# MCU.net
KiCad netlist of a schematic drawn in Altium Designer
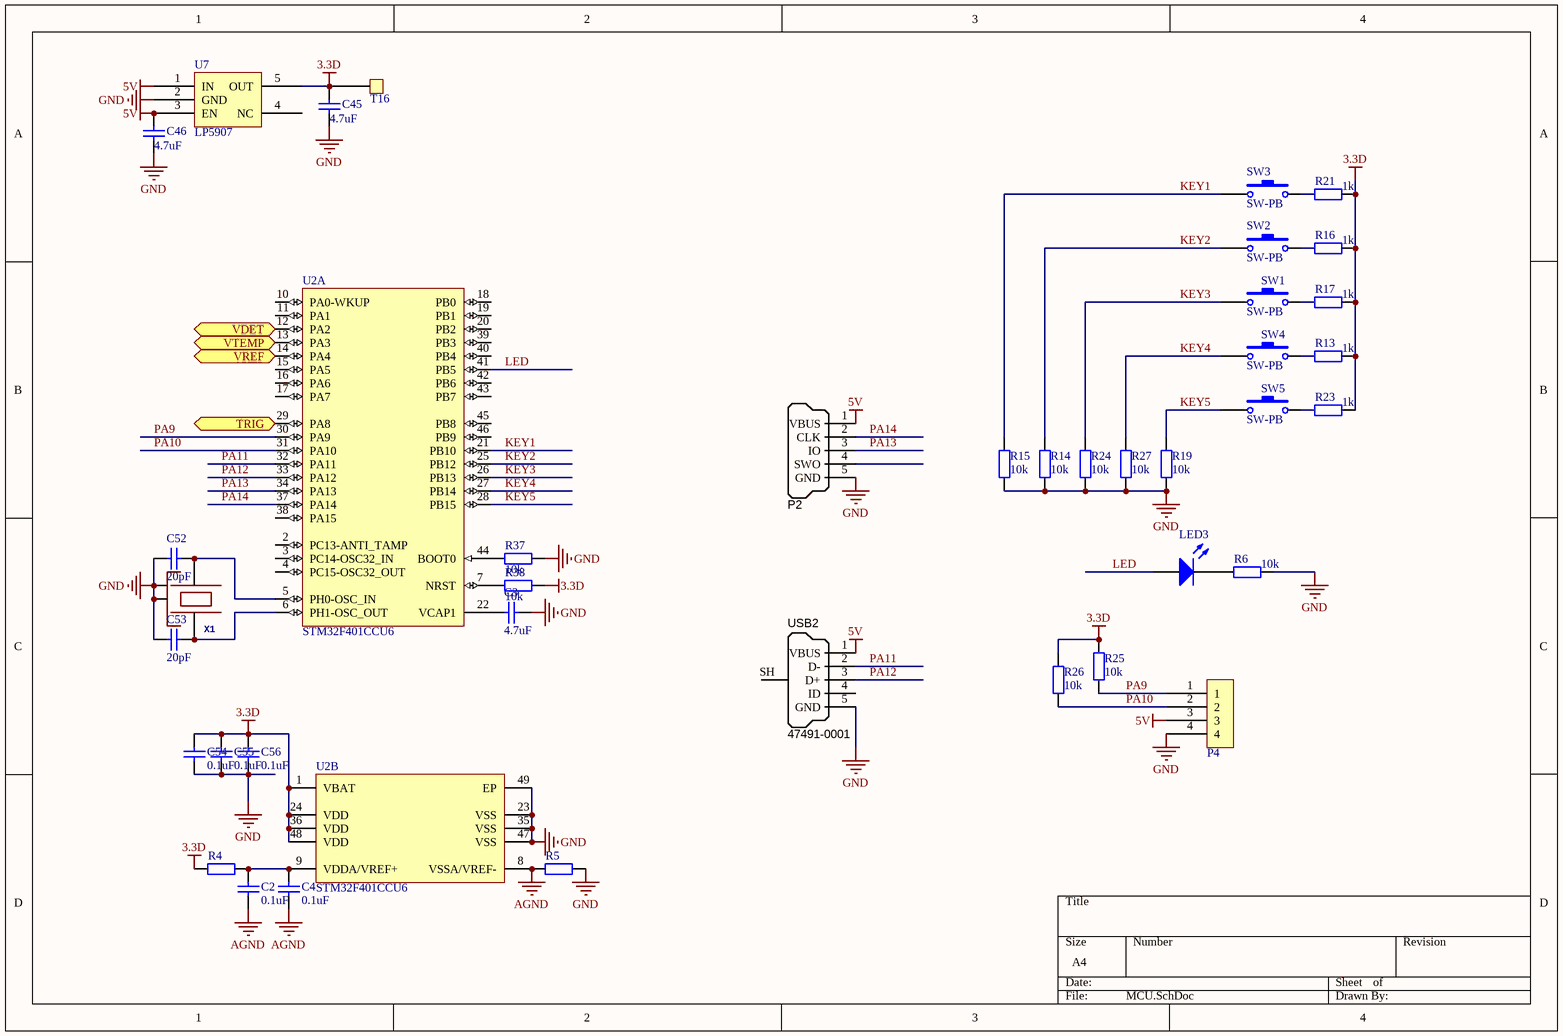
[diagram p0: MCU.SchDoc]

(export (version "E")
  (design (tool "Eeschema 10.0.6"))
  (components
    (comp (ref "C2")
      (value "0.1uF")
      (footprint "0402")
      (description "Capacitor")
      (fields (field (name "Comment") "Cap") (field (name "PUBLISHER") "Altium Limited"))
      (libsource (lib "RTC6705") (part "Cap"))
    )
    (comp (ref "C3")
      (value "4.7uF")
      (footprint "0603")
      (description "Capacitor")
      (fields (field (name "Comment") "Cap") (field (name "PUBLISHER") "Altium Limited"))
      (libsource (lib "RTC6705") (part "Cap"))
    )
    (comp (ref "C4")
      (value "0.1uF")
      (footprint "0402")
      (description "Capacitor")
      (fields (field (name "Comment") "Cap") (field (name "PUBLISHER") "Altium Limited"))
      (libsource (lib "RTC6705") (part "Cap"))
    )
    (comp (ref "C45")
      (value "4.7uF")
      (footprint "0603")
      (description "Capacitor")
      (fields (field (name "PUBLISHER") "Altium Limited"))
      (libsource (lib "RTC6705") (part "Cap"))
    )
    (comp (ref "C46")
      (value "4.7uF")
      (footprint "0603")
      (description "Capacitor")
      (fields (field (name "PUBLISHER") "Altium Limited"))
      (libsource (lib "RTC6705") (part "Cap"))
    )
    (comp (ref "C52")
      (value "20pF")
      (footprint "0402")
      (description "Capacitor")
      (fields (field (name "Comment") "Cap") (field (name "PUBLISHER") "Altium Limited"))
      (libsource (lib "RTC6705") (part "Cap"))
    )
    (comp (ref "C53")
      (value "20pF")
      (footprint "0402")
      (description "Capacitor")
      (fields (field (name "Comment") "Cap") (field (name "PUBLISHER") "Altium Limited"))
      (libsource (lib "RTC6705") (part "Cap"))
    )
    (comp (ref "C54")
      (value "0.1uF")
      (footprint "0402")
      (description "Capacitor")
      (fields (field (name "Comment") "Cap") (field (name "PUBLISHER") "Altium Limited"))
      (libsource (lib "RTC6705") (part "Cap"))
    )
    (comp (ref "C55")
      (value "0.1uF")
      (footprint "0402")
      (description "Capacitor")
      (fields (field (name "Comment") "Cap") (field (name "PUBLISHER") "Altium Limited"))
      (libsource (lib "RTC6705") (part "Cap"))
    )
    (comp (ref "C56")
      (value "0.1uF")
      (footprint "0402")
      (description "Capacitor")
      (fields (field (name "Comment") "Cap") (field (name "PUBLISHER") "Altium Limited"))
      (libsource (lib "RTC6705") (part "Cap"))
    )
    (comp (ref "LED3")
      (value "LED0")
      (footprint "0603")
      (description "Typical INFRARED GaAs LED")
      (fields (field (name "PUBLISHER") "Altium Limited"))
      (libsource (lib "Miscellaneous Devices") (part "LED0"))
    )
    (comp (ref "P2")
      (value "SWD_MicroUSB")
      (footprint "MICRO-YZX")
      (description "Connector SMD USB Micro Type B middle mount")
      (libsource (lib "sch") (part "SWD_MicroUSB"))
    )
    (comp (ref "P4") (value "UART/I2C") (footprint "4pSocket") (libsource (lib "sch") (part "4PSocket")))
    (comp (ref "R4")
      (value "0R/FB")
      (footprint "0402")
      (description "Resistor")
      (fields (field (name "PUBLISHER") "Altium Limited"))
      (libsource (lib "RTC6705") (part "Res2"))
    )
    (comp (ref "R5")
      (value "0R/FB")
      (footprint "0402")
      (description "Resistor")
      (fields (field (name "PUBLISHER") "Altium Limited"))
      (libsource (lib "RTC6705") (part "Res2"))
    )
    (comp (ref "R6")
      (value "10k")
      (footprint "0402")
      (description "Resistor")
      (fields (field (name "PUBLISHER") "Altium Limited"))
      (libsource (lib "Miscellaneous Devices") (part "Res2"))
    )
    (comp (ref "R13")
      (value "1k")
      (footprint "0402")
      (description "Resistor")
      (fields (field (name "PUBLISHER") "Altium Limited"))
      (libsource (lib "Miscellaneous Devices") (part "Res2"))
    )
    (comp (ref "R14")
      (value "10k")
      (footprint "0402")
      (description "Resistor")
      (fields (field (name "PUBLISHER") "Altium Limited"))
      (libsource (lib "") (part "Res2_1"))
    )
    (comp (ref "R15")
      (value "10k")
      (footprint "0402")
      (description "Resistor")
      (fields (field (name "PUBLISHER") "Altium Limited"))
      (libsource (lib "") (part "Res2_1"))
    )
    (comp (ref "R16")
      (value "1k")
      (footprint "0402")
      (description "Resistor")
      (fields (field (name "PUBLISHER") "Altium Limited"))
      (libsource (lib "Miscellaneous Devices") (part "Res2"))
    )
    (comp (ref "R17")
      (value "1k")
      (footprint "0402")
      (description "Resistor")
      (fields (field (name "PUBLISHER") "Altium Limited"))
      (libsource (lib "Miscellaneous Devices") (part "Res2"))
    )
    (comp (ref "R19")
      (value "10k")
      (footprint "0402")
      (description "Resistor")
      (fields (field (name "PUBLISHER") "Altium Limited"))
      (libsource (lib "") (part "Res2_1"))
    )
    (comp (ref "R21")
      (value "1k")
      (footprint "0402")
      (description "Resistor")
      (fields (field (name "PUBLISHER") "Altium Limited"))
      (libsource (lib "Miscellaneous Devices") (part "Res2"))
    )
    (comp (ref "R23")
      (value "1k")
      (footprint "0402")
      (description "Resistor")
      (fields (field (name "PUBLISHER") "Altium Limited"))
      (libsource (lib "Miscellaneous Devices") (part "Res2"))
    )
    (comp (ref "R24")
      (value "10k")
      (footprint "0402")
      (description "Resistor")
      (fields (field (name "PUBLISHER") "Altium Limited"))
      (libsource (lib "") (part "Res2_1"))
    )
    (comp (ref "R25")
      (value "10k")
      (footprint "0402")
      (description "Resistor")
      (fields (field (name "PUBLISHER") "Altium Limited"))
      (libsource (lib "") (part "Res2_1"))
    )
    (comp (ref "R26")
      (value "10k")
      (footprint "0402")
      (description "Resistor")
      (fields (field (name "PUBLISHER") "Altium Limited"))
      (libsource (lib "") (part "Res2_1"))
    )
    (comp (ref "R27")
      (value "10k")
      (footprint "0402")
      (description "Resistor")
      (fields (field (name "PUBLISHER") "Altium Limited"))
      (libsource (lib "") (part "Res2_1"))
    )
    (comp (ref "R37")
      (value "10k")
      (footprint "0402")
      (description "Resistor")
      (fields (field (name "Comment") "Res2") (field (name "PUBLISHER") "Altium Limited"))
      (libsource (lib "") (part "Res2_1"))
    )
    (comp (ref "R38")
      (value "10k")
      (footprint "0402")
      (description "Resistor")
      (fields (field (name "Comment") "Res2") (field (name "PUBLISHER") "Altium Limited"))
      (libsource (lib "RTC6705") (part "Res2"))
    )
    (comp (ref "SW1")
      (value "SW-PB")
      (footprint "SW3x4")
      (description "Switch")
      (fields (field (name "PUBLISHER") "Altium Limited"))
      (libsource (lib "Miscellaneous Devices") (part "SW-PB"))
    )
    (comp (ref "SW2")
      (value "SW-PB")
      (footprint "SW3x4")
      (description "Switch")
      (fields (field (name "PUBLISHER") "Altium Limited"))
      (libsource (lib "Miscellaneous Devices") (part "SW-PB"))
    )
    (comp (ref "SW3")
      (value "SW-PB")
      (footprint "SW3x4")
      (description "Switch")
      (fields (field (name "PUBLISHER") "Altium Limited"))
      (libsource (lib "Miscellaneous Devices") (part "SW-PB"))
    )
    (comp (ref "SW4")
      (value "SW-PB")
      (footprint "SW3x4")
      (description "Switch")
      (fields (field (name "PUBLISHER") "Altium Limited"))
      (libsource (lib "Miscellaneous Devices") (part "SW-PB"))
    )
    (comp (ref "SW5")
      (value "SW-PB")
      (footprint "SW3x4")
      (description "Switch")
      (fields (field (name "PUBLISHER") "Altium Limited"))
      (libsource (lib "Miscellaneous Devices") (part "SW-PB"))
    )
    (comp (ref "T16") (value "TestPad") (footprint "TestPad - 1mm") (libsource (lib "sch") (part "TestPad")))
    (comp (ref "U2")
      (value "STM32F401CCU6")
      (footprint "STM-UFQFPN48_N")
      (fields (field (name "MANUFACTURER") "STMicroelectronics"))
      (libsource (lib "STMicroelectronics STM32 F4") (part "STM32F401CCU6"))
    )
    (comp (ref "U7") (value "LP5907") (footprint "SOT23-5") (libsource (lib "RTC6705") (part "LP5907")))
    (comp (ref "USB2")
      (value "USB Micro Type B")
      (footprint "MICRO-YZX")
      (description "Connector SMD USB Micro Type B middle mount")
      (fields (field (name "MANUFACTURER PART NUMBER 1") "47491-0001"))
      (libsource (lib "PBL - Connectors") (part "USB_Micro_TypeB"))
    )
    (comp (ref "X1")
      (value "24.000 KHz 3.2x2.5mm 8-10pf")
      (footprint "OSCILLATOR-3.2X2.5")
      (description "Crystal Oscillator in 3.2x2.5 SMD")
      (libsource (lib "pixhawk2") (part "OSCILLATOR-3.2X2.5"))
    )
  )
  (nets
    (net (code "1") (name "/KEY1") (class "Default")
      (node (ref "R15") (pin "2") (pinfunction "2_2") (pintype "passive"))
      (node (ref "SW3") (pin "1") (pinfunction "1_1") (pintype "passive"))
      (node (ref "U2") (pin "21") (pinfunction "PB10_21") (pintype "bidirectional"))
    )
    (net (code "2") (name "/KEY2") (class "Default")
      (node (ref "R14") (pin "2") (pinfunction "2_2") (pintype "passive"))
      (node (ref "SW2") (pin "1") (pinfunction "1_1") (pintype "passive"))
      (node (ref "U2") (pin "25") (pinfunction "PB12_25") (pintype "bidirectional"))
    )
    (net (code "3") (name "/KEY3") (class "Default")
      (node (ref "R24") (pin "2") (pinfunction "2_2") (pintype "passive"))
      (node (ref "SW1") (pin "1") (pinfunction "1_1") (pintype "passive"))
      (node (ref "U2") (pin "26") (pinfunction "PB13_26") (pintype "bidirectional"))
    )
    (net (code "4") (name "/KEY4") (class "Default")
      (node (ref "R27") (pin "2") (pinfunction "2_2") (pintype "passive"))
      (node (ref "SW4") (pin "1") (pinfunction "1_1") (pintype "passive"))
      (node (ref "U2") (pin "27") (pinfunction "PB14_27") (pintype "bidirectional"))
    )
    (net (code "5") (name "/KEY5") (class "Default")
      (node (ref "R19") (pin "2") (pinfunction "2_2") (pintype "passive"))
      (node (ref "SW5") (pin "1") (pinfunction "1_1") (pintype "passive"))
      (node (ref "U2") (pin "28") (pinfunction "PB15_28") (pintype "bidirectional"))
    )
    (net (code "6") (name "/LED") (class "Default")
      (node (ref "LED3") (pin "1") (pinfunction "A_1") (pintype "passive"))
      (node (ref "U2") (pin "41") (pinfunction "PB5_41") (pintype "bidirectional"))
    )
    (net (code "7") (name "/PA9") (class "Default")
      (node (ref "P4") (pin "1") (pinfunction "1_1") (pintype "passive"))
      (node (ref "R25") (pin "1") (pinfunction "1_1") (pintype "passive"))
      (node (ref "U2") (pin "30") (pinfunction "PA9_30") (pintype "bidirectional"))
    )
    (net (code "8") (name "/PA10") (class "Default")
      (node (ref "P4") (pin "2") (pinfunction "2_2") (pintype "passive"))
      (node (ref "R26") (pin "1") (pinfunction "1_1") (pintype "passive"))
      (node (ref "U2") (pin "31") (pinfunction "PA10_31") (pintype "bidirectional"))
    )
    (net (code "9") (name "/PA11") (class "Default")
      (node (ref "U2") (pin "32") (pinfunction "PA11_32") (pintype "bidirectional"))
      (node (ref "USB2") (pin "2") (pinfunction "D-_2") (pintype "passive"))
    )
    (net (code "10") (name "/PA12") (class "Default")
      (node (ref "U2") (pin "33") (pinfunction "PA12_33") (pintype "bidirectional"))
      (node (ref "USB2") (pin "3") (pinfunction "D+_3") (pintype "passive"))
    )
    (net (code "11") (name "/PA13") (class "Default")
      (node (ref "P2") (pin "3") (pinfunction "IO_3") (pintype "passive"))
      (node (ref "U2") (pin "34") (pinfunction "PA13_34") (pintype "bidirectional"))
    )
    (net (code "12") (name "/PA14") (class "Default")
      (node (ref "P2") (pin "2") (pinfunction "CLK_2") (pintype "passive"))
      (node (ref "U2") (pin "37") (pinfunction "PA14_37") (pintype "bidirectional"))
    )
    (net (code "13") (name "/TRIG") (class "Default")
      (node (ref "U2") (pin "29") (pinfunction "PA8_29") (pintype "bidirectional"))
    )
    (net (code "14") (name "/VDET") (class "Default")
      (node (ref "U2") (pin "12") (pinfunction "PA2_12") (pintype "bidirectional"))
    )
    (net (code "15") (name "/VREF") (class "Default")
      (node (ref "U2") (pin "14") (pinfunction "PA4_14") (pintype "bidirectional"))
    )
    (net (code "16") (name "/VTEMP") (class "Default")
      (node (ref "U2") (pin "13") (pinfunction "PA3_13") (pintype "bidirectional"))
    )
    (net (code "17") (name "3.3D") (class "Default")
      (node (ref "C45") (pin "2") (pinfunction "2_2") (pintype "passive"))
      (node (ref "C54") (pin "2") (pinfunction "2_2") (pintype "passive"))
      (node (ref "C55") (pin "2") (pinfunction "2_2") (pintype "passive"))
      (node (ref "C56") (pin "2") (pinfunction "2_2") (pintype "passive"))
      (node (ref "R13") (pin "2") (pinfunction "2_2") (pintype "passive"))
      (node (ref "R16") (pin "2") (pinfunction "2_2") (pintype "passive"))
      (node (ref "R17") (pin "2") (pinfunction "2_2") (pintype "passive"))
      (node (ref "R21") (pin "2") (pinfunction "2_2") (pintype "passive"))
      (node (ref "R23") (pin "2") (pinfunction "2_2") (pintype "passive"))
      (node (ref "R25") (pin "2") (pinfunction "2_2") (pintype "passive"))
      (node (ref "R26") (pin "2") (pinfunction "2_2") (pintype "passive"))
      (node (ref "R38") (pin "1") (pinfunction "1_1") (pintype "passive"))
      (node (ref "R4") (pin "2") (pinfunction "2_2") (pintype "passive"))
      (node (ref "T16") (pin "1") (pinfunction "3_1") (pintype "passive"))
      (node (ref "U2") (pin "1") (pinfunction "VBAT_1") (pintype "power_in"))
      (node (ref "U2") (pin "24") (pinfunction "VDD_24") (pintype "power_in"))
      (node (ref "U2") (pin "36") (pinfunction "VDD_36") (pintype "power_in"))
      (node (ref "U2") (pin "48") (pinfunction "VDD_48") (pintype "power_in"))
      (node (ref "U7") (pin "5") (pinfunction "OUT_5") (pintype "passive"))
    )
    (net (code "18") (name "5V") (class "Default")
      (node (ref "C46") (pin "2") (pinfunction "2_2") (pintype "passive"))
      (node (ref "P2") (pin "1") (pinfunction "VBUS_1") (pintype "passive"))
      (node (ref "P4") (pin "3") (pinfunction "3_3") (pintype "passive"))
      (node (ref "U7") (pin "1") (pinfunction "IN_1") (pintype "passive"))
      (node (ref "U7") (pin "3") (pinfunction "EN_3") (pintype "passive"))
      (node (ref "USB2") (pin "1") (pinfunction "VBUS_1") (pintype "passive"))
    )
    (net (code "19") (name "AGND") (class "Default")
      (node (ref "C2") (pin "1") (pinfunction "1_1") (pintype "passive"))
      (node (ref "C4") (pin "1") (pinfunction "1_1") (pintype "passive"))
      (node (ref "R5") (pin "2") (pinfunction "2_2") (pintype "passive"))
      (node (ref "U2") (pin "8") (pinfunction "VSSA/VREF-_8") (pintype "power_in"))
    )
    (net (code "20") (name "GND") (class "Default")
      (node (ref "C3") (pin "1") (pinfunction "1_1") (pintype "passive"))
      (node (ref "C45") (pin "1") (pinfunction "1_1") (pintype "passive"))
      (node (ref "C46") (pin "1") (pinfunction "1_1") (pintype "passive"))
      (node (ref "C52") (pin "1") (pinfunction "1_1") (pintype "passive"))
      (node (ref "C53") (pin "1") (pinfunction "1_1") (pintype "passive"))
      (node (ref "C54") (pin "1") (pinfunction "1_1") (pintype "passive"))
      (node (ref "C55") (pin "1") (pinfunction "1_1") (pintype "passive"))
      (node (ref "C56") (pin "1") (pinfunction "1_1") (pintype "passive"))
      (node (ref "P2") (pin "5") (pinfunction "GND_5") (pintype "passive"))
      (node (ref "P4") (pin "4") (pinfunction "4_4") (pintype "passive"))
      (node (ref "R14") (pin "1") (pinfunction "1_1") (pintype "passive"))
      (node (ref "R15") (pin "1") (pinfunction "1_1") (pintype "passive"))
      (node (ref "R19") (pin "1") (pinfunction "1_1") (pintype "passive"))
      (node (ref "R24") (pin "1") (pinfunction "1_1") (pintype "passive"))
      (node (ref "R27") (pin "1") (pinfunction "1_1") (pintype "passive"))
      (node (ref "R37") (pin "2") (pinfunction "2_2") (pintype "passive"))
      (node (ref "R5") (pin "1") (pinfunction "1_1") (pintype "passive"))
      (node (ref "R6") (pin "2") (pinfunction "2_2") (pintype "passive"))
      (node (ref "U2") (pin "23") (pinfunction "VSS_23") (pintype "power_in"))
      (node (ref "U2") (pin "35") (pinfunction "VSS_35") (pintype "power_in"))
      (node (ref "U2") (pin "47") (pinfunction "VSS_47") (pintype "power_in"))
      (node (ref "U2") (pin "49") (pinfunction "EP_49") (pintype "power_in"))
      (node (ref "U7") (pin "2") (pinfunction "GND_2") (pintype "passive"))
      (node (ref "USB2") (pin "5") (pinfunction "GND_5") (pintype "passive"))
      (node (ref "X1") (pin "2") (pinfunction "NC_2_2") (pintype "open_emitter"))
      (node (ref "X1") (pin "4") (pinfunction "NC_4_4") (pintype "open_emitter"))
    )
    (net (code "21") (name "Net-(LED3-K)") (class "Default")
      (node (ref "LED3") (pin "2") (pinfunction "K_2") (pintype "passive"))
      (node (ref "R6") (pin "1") (pinfunction "1_1") (pintype "passive"))
    )
    (net (code "22") (name "Net-(R13-Pad1)") (class "Default")
      (node (ref "R13") (pin "1") (pinfunction "1_1") (pintype "passive"))
      (node (ref "SW4") (pin "2") (pinfunction "2_2") (pintype "passive"))
    )
    (net (code "23") (name "Net-(R16-Pad1)") (class "Default")
      (node (ref "R16") (pin "1") (pinfunction "1_1") (pintype "passive"))
      (node (ref "SW2") (pin "2") (pinfunction "2_2") (pintype "passive"))
    )
    (net (code "24") (name "Net-(R17-Pad1)") (class "Default")
      (node (ref "R17") (pin "1") (pinfunction "1_1") (pintype "passive"))
      (node (ref "SW1") (pin "2") (pinfunction "2_2") (pintype "passive"))
    )
    (net (code "25") (name "Net-(R21-Pad1)") (class "Default")
      (node (ref "R21") (pin "1") (pinfunction "1_1") (pintype "passive"))
      (node (ref "SW3") (pin "2") (pinfunction "2_2") (pintype "passive"))
    )
    (net (code "26") (name "Net-(R23-Pad1)") (class "Default")
      (node (ref "R23") (pin "1") (pinfunction "1_1") (pintype "passive"))
      (node (ref "SW5") (pin "2") (pinfunction "2_2") (pintype "passive"))
    )
    (net (code "27") (name "Net-(U2A-BOOT0)") (class "Default")
      (node (ref "R37") (pin "1") (pinfunction "1_1") (pintype "passive"))
      (node (ref "U2") (pin "44") (pinfunction "BOOT0_44") (pintype "input"))
    )
    (net (code "28") (name "Net-(U2A-NRST)") (class "Default")
      (node (ref "R38") (pin "2") (pinfunction "2_2") (pintype "passive"))
      (node (ref "U2") (pin "7") (pinfunction "NRST_7") (pintype "bidirectional"))
    )
    (net (code "29") (name "Net-(U2A-PH0-OSC_IN)") (class "Default")
      (node (ref "C52") (pin "2") (pinfunction "2_2") (pintype "passive"))
      (node (ref "U2") (pin "5") (pinfunction "PH0-OSC_IN_5") (pintype "bidirectional"))
      (node (ref "X1") (pin "1") (pinfunction "1_1") (pintype "passive"))
    )
    (net (code "30") (name "Net-(U2A-PH1-OSC_OUT)") (class "Default")
      (node (ref "C53") (pin "2") (pinfunction "2_2") (pintype "passive"))
      (node (ref "U2") (pin "6") (pinfunction "PH1-OSC_OUT_6") (pintype "bidirectional"))
      (node (ref "X1") (pin "3") (pinfunction "3_3") (pintype "passive"))
    )
    (net (code "31") (name "Net-(U2A-VCAP1)") (class "Default")
      (node (ref "C3") (pin "2") (pinfunction "2_2") (pintype "passive"))
      (node (ref "U2") (pin "22") (pinfunction "VCAP1_22") (pintype "power_in"))
    )
    (net (code "32") (name "Net-(U2B-VDDA{slash}VREF+)") (class "Default")
      (node (ref "C2") (pin "2") (pinfunction "2_2") (pintype "passive"))
      (node (ref "C4") (pin "2") (pinfunction "2_2") (pintype "passive"))
      (node (ref "R4") (pin "1") (pinfunction "1_1") (pintype "passive"))
      (node (ref "U2") (pin "9") (pinfunction "VDDA/VREF+_9") (pintype "power_in"))
    )
    (net (code "33") (name "unconnected-(P2-SWO-Pad4)") (class "Default")
      (node (ref "P2") (pin "4") (pinfunction "SWO_4") (pintype "passive"))
    )
    (net (code "34") (name "unconnected-(U2A-PA0-WKUP-Pad10)") (class "Default")
      (node (ref "U2") (pin "10") (pinfunction "PA0-WKUP_10") (pintype "bidirectional"))
    )
    (net (code "35") (name "unconnected-(U2A-PA1-Pad11)") (class "Default")
      (node (ref "U2") (pin "11") (pinfunction "PA1_11") (pintype "bidirectional"))
    )
    (net (code "36") (name "unconnected-(U2A-PA5-Pad15)") (class "Default")
      (node (ref "U2") (pin "15") (pinfunction "PA5_15") (pintype "bidirectional"))
    )
    (net (code "37") (name "unconnected-(U2A-PA6-Pad16)") (class "Default")
      (node (ref "U2") (pin "16") (pinfunction "PA6_16") (pintype "bidirectional"))
    )
    (net (code "38") (name "unconnected-(U2A-PA7-Pad17)") (class "Default")
      (node (ref "U2") (pin "17") (pinfunction "PA7_17") (pintype "bidirectional"))
    )
    (net (code "39") (name "unconnected-(U2A-PA15-Pad38)") (class "Default")
      (node (ref "U2") (pin "38") (pinfunction "PA15_38") (pintype "bidirectional"))
    )
    (net (code "40") (name "unconnected-(U2A-PB0-Pad18)") (class "Default")
      (node (ref "U2") (pin "18") (pinfunction "PB0_18") (pintype "bidirectional"))
    )
    (net (code "41") (name "unconnected-(U2A-PB1-Pad19)") (class "Default")
      (node (ref "U2") (pin "19") (pinfunction "PB1_19") (pintype "bidirectional"))
    )
    (net (code "42") (name "unconnected-(U2A-PB2-Pad20)") (class "Default")
      (node (ref "U2") (pin "20") (pinfunction "PB2_20") (pintype "bidirectional"))
    )
    (net (code "43") (name "unconnected-(U2A-PB3-Pad39)") (class "Default")
      (node (ref "U2") (pin "39") (pinfunction "PB3_39") (pintype "bidirectional"))
    )
    (net (code "44") (name "unconnected-(U2A-PB4-Pad40)") (class "Default")
      (node (ref "U2") (pin "40") (pinfunction "PB4_40") (pintype "bidirectional"))
    )
    (net (code "45") (name "unconnected-(U2A-PB6-Pad42)") (class "Default")
      (node (ref "U2") (pin "42") (pinfunction "PB6_42") (pintype "bidirectional"))
    )
    (net (code "46") (name "unconnected-(U2A-PB7-Pad43)") (class "Default")
      (node (ref "U2") (pin "43") (pinfunction "PB7_43") (pintype "bidirectional"))
    )
    (net (code "47") (name "unconnected-(U2A-PB8-Pad45)") (class "Default")
      (node (ref "U2") (pin "45") (pinfunction "PB8_45") (pintype "bidirectional"))
    )
    (net (code "48") (name "unconnected-(U2A-PB9-Pad46)") (class "Default")
      (node (ref "U2") (pin "46") (pinfunction "PB9_46") (pintype "bidirectional"))
    )
    (net (code "49") (name "unconnected-(U2A-PC13-ANTI_TAMP-Pad2)") (class "Default")
      (node (ref "U2") (pin "2") (pinfunction "PC13-ANTI_TAMP_2") (pintype "bidirectional"))
    )
    (net (code "50") (name "unconnected-(U2A-PC14-OSC32_IN-Pad3)") (class "Default")
      (node (ref "U2") (pin "3") (pinfunction "PC14-OSC32_IN_3") (pintype "bidirectional"))
    )
    (net (code "51") (name "unconnected-(U2A-PC15-OSC32_OUT-Pad4)") (class "Default")
      (node (ref "U2") (pin "4") (pinfunction "PC15-OSC32_OUT_4") (pintype "bidirectional"))
    )
    (net (code "52") (name "unconnected-(U7-NC-Pad4)") (class "Default")
      (node (ref "U7") (pin "4") (pinfunction "NC_4") (pintype "passive"))
    )
    (net (code "53") (name "unconnected-(USB2-ID-Pad4)") (class "Default")
      (node (ref "USB2") (pin "4") (pinfunction "ID_4") (pintype "passive"))
    )
    (net (code "54") (name "unconnected-(USB2-Shell-PadSH)") (class "Default")
      (node (ref "USB2") (pin "SH") (pinfunction "Shell_SH") (pintype "passive"))
    )
  )
)
